# DATA_recorder.net
KiCad netlist of a schematic drawn in EasyEDA
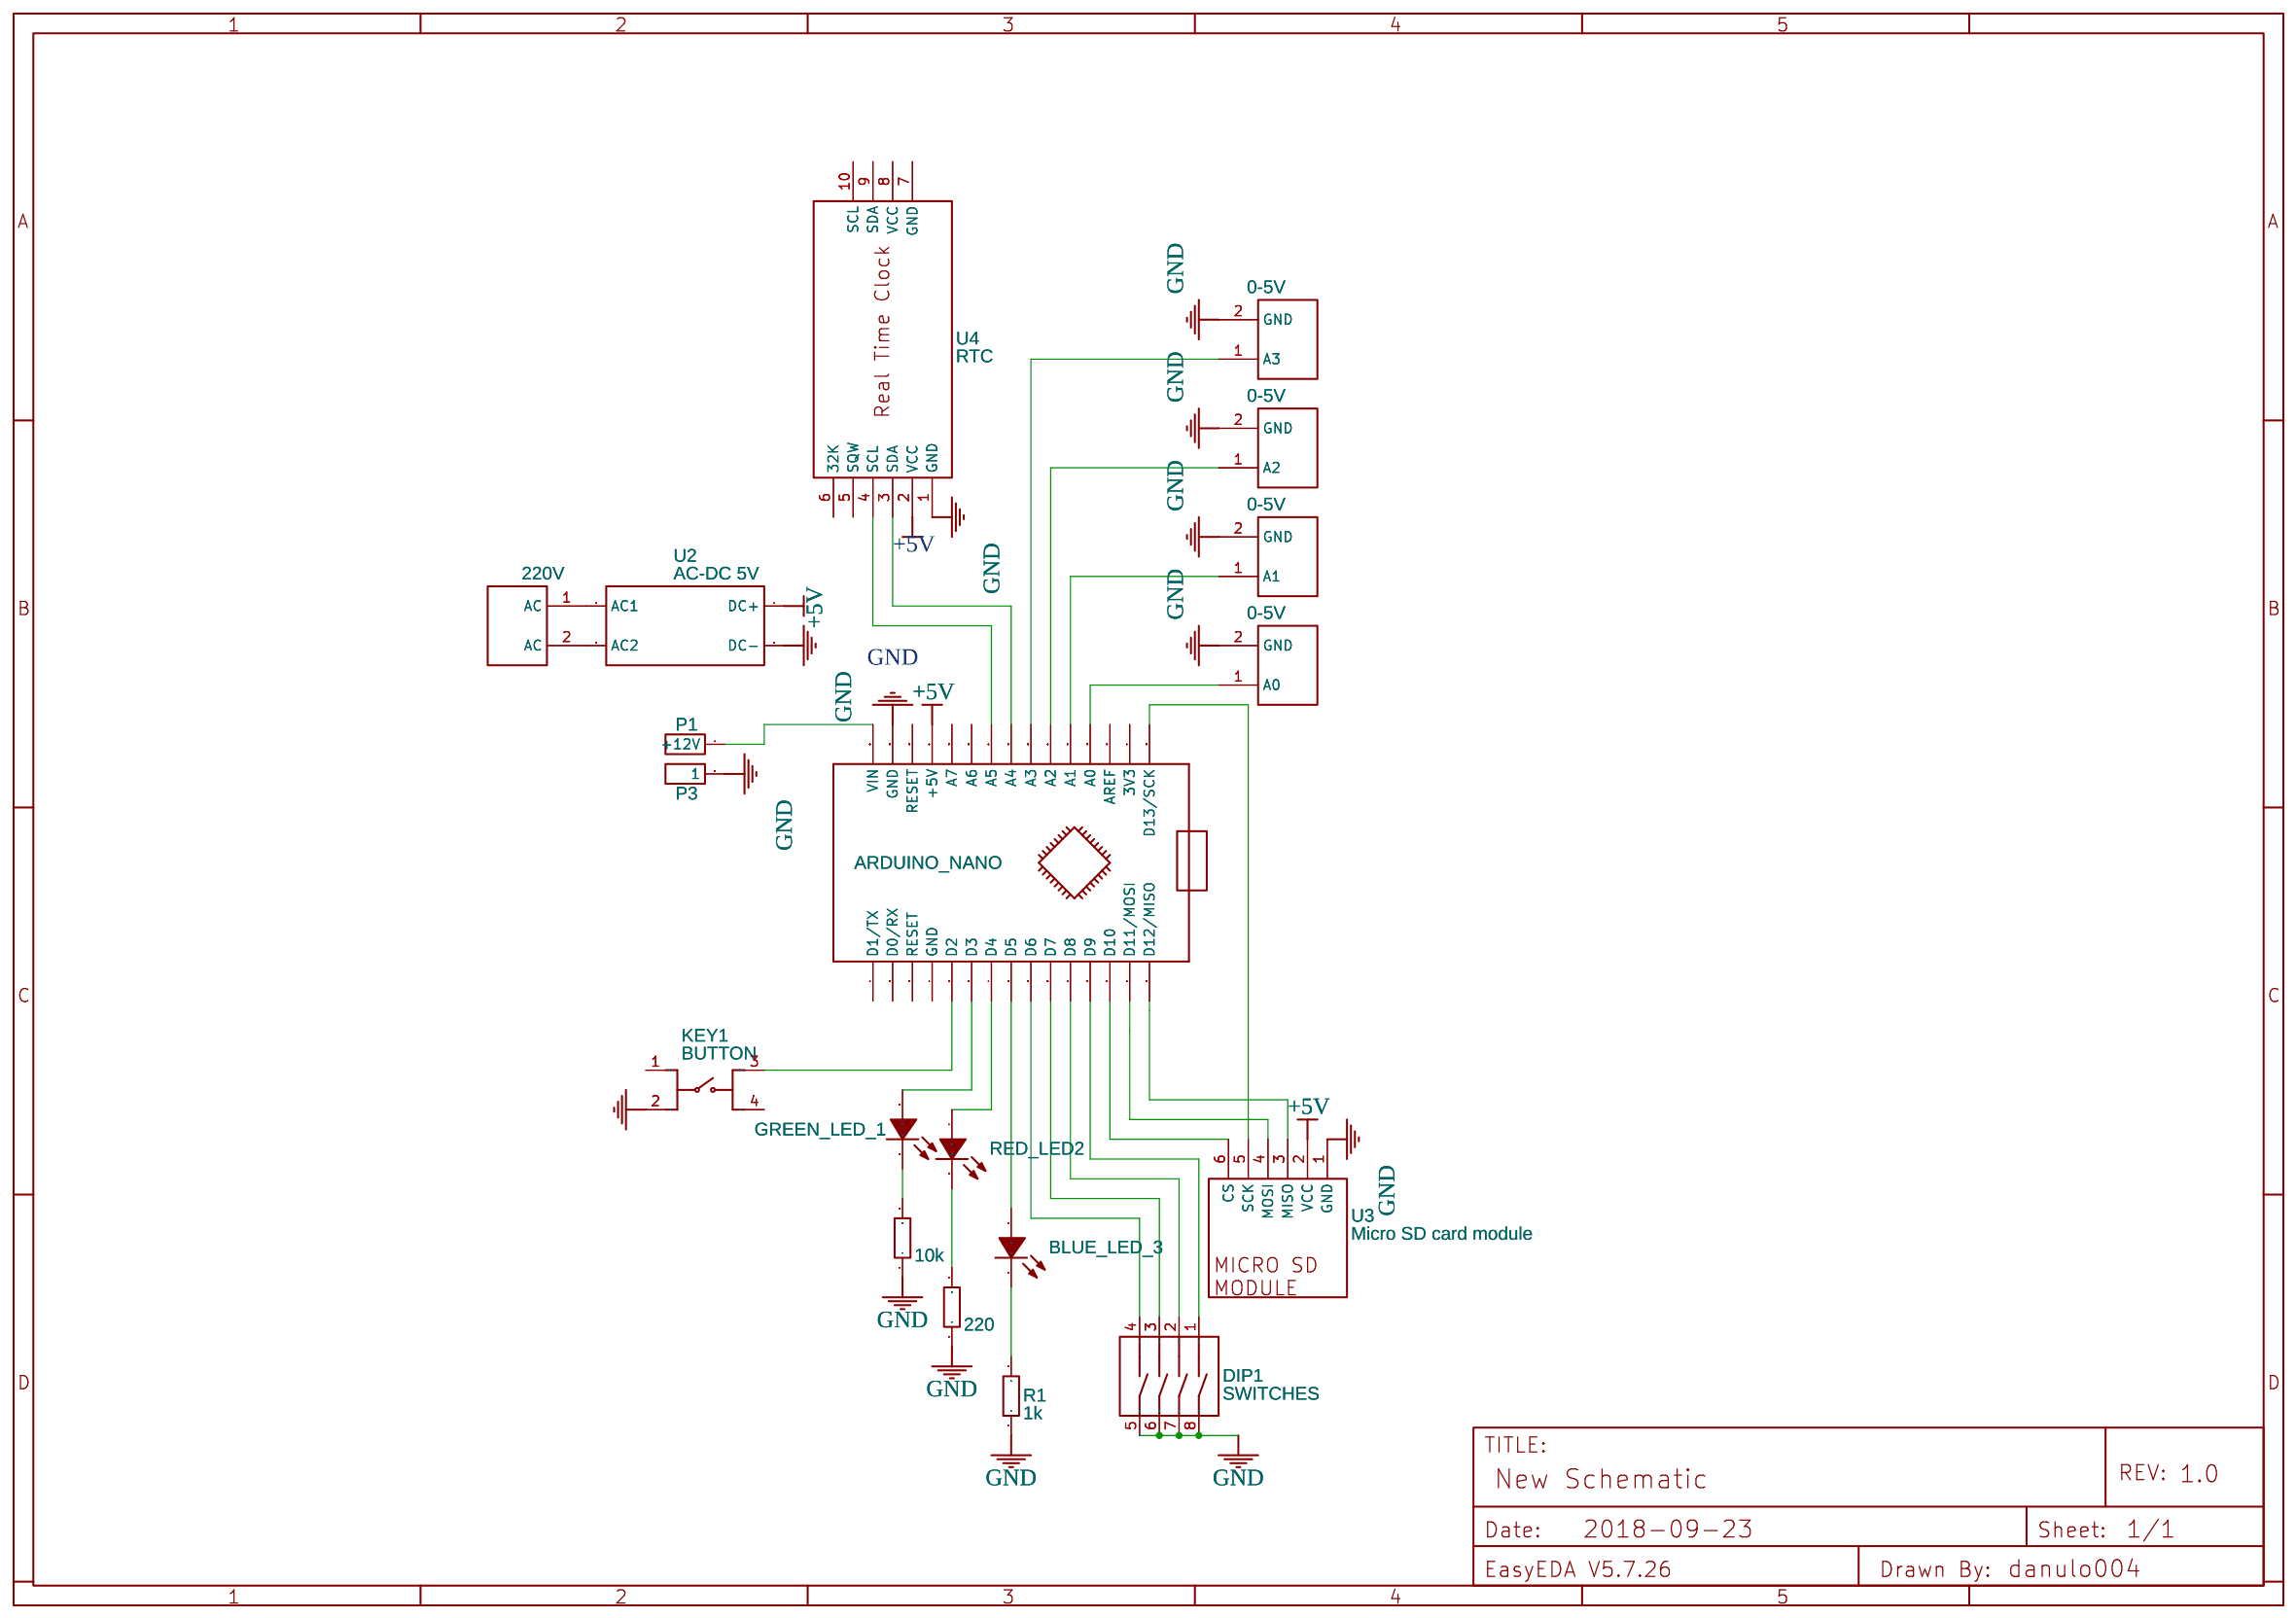
[diagram p0: schematic sheet]

(export (version "E")
  (design (tool "Eeschema 10.0.6"))
  (components
    (comp (ref "BLUE_LED_3")
      (value "LEDOrange orange 3AO4UD")
      (fields (field (name "BOM_Supplier Part") "C62095"))
      (libsource (lib "") (part "Unknown_505_625"))
    )
    (comp (ref "C")
      (value "220V")
      (fields (field (name "BOM_Manufacturer Part") "?"))
      (libsource (lib "") (part "Unknown_260_310"))
    )
    (comp (ref "CN1")
      (value "0-5V")
      (fields (field (name "BOM_Manufacturer Part") "?"))
      (libsource (lib "") (part "Unknown_640_330"))
    )
    (comp (ref "CN2")
      (value "0-5V")
      (fields (field (name "BOM_Manufacturer Part") "?"))
      (libsource (lib "") (part "Unknown_640_275"))
    )
    (comp (ref "CN3")
      (value "0-5V")
      (fields (field (name "BOM_Manufacturer Part") "?"))
      (libsource (lib "") (part "Unknown_640_220"))
    )
    (comp (ref "CN4")
      (value "0-5V")
      (fields (field (name "BOM_Manufacturer Part") "?"))
      (libsource (lib "") (part "Unknown_640_165"))
    )
    (comp (ref "DIP1")
      (value "SWITCHES")
      (fields
        (field (name "BOM_Manufacturer Part") "VDG/S-04HG-R")
        (field (name "BOM_Supplier Part") "C15781")
      )
      (libsource (lib "") (part "Unknown_585_690"))
    )
    (comp (ref "GREEN_LED_1")
      (value "LEDOrange orange 3AO4UD")
      (fields (field (name "BOM_Supplier Part") "C62095"))
      (libsource (lib "") (part "Unknown_450_565"))
    )
    (comp (ref "KEY1")
      (value "BUTTON")
      (fields
        (field (name "BOM_Manufacturer Part") "TS-1102-5016")
        (field (name "BOM_Supplier Part") "C111609")
      )
      (libsource (lib "") (part "Unknown_350_545"))
    )
    (comp (ref "P1")
      (value "Header-Male-2.54_1x1")
      (fields (field (name "BOM_Supplier Part") "C81276"))
      (libsource (lib "") (part "Unknown_345_370"))
    )
    (comp (ref "P3")
      (value "Header-Male-2.54_1x1")
      (fields (field (name "BOM_Supplier Part") "C81276"))
      (libsource (lib "") (part "Unknown_345_385"))
    )
    (comp (ref "R1")
      (value "1k")
      (fields (field (name "BOM_Manufacturer Part") "?"))
      (libsource (lib "") (part "Res_AXIAL-0.4(1/4W)_EU"))
    )
    (comp (ref "R2")
      (value "220")
      (fields (field (name "BOM_Manufacturer Part") "?"))
      (libsource (lib "") (part "Res_AXIAL-0.4(1/4W)_EU"))
    )
    (comp (ref "R3")
      (value "10k")
      (fields (field (name "BOM_Manufacturer Part") "?"))
      (libsource (lib "") (part "Res_AXIAL-0.4(1/4W)_EU"))
    )
    (comp (ref "RED_LED2")
      (value "LEDOrange orange 3AO4UD")
      (fields (field (name "BOM_Supplier Part") "C62095"))
      (libsource (lib "") (part "Unknown_475_575"))
    )
    (comp (ref "U1")
      (value "ARDUINO_NANO")
      (fields (field (name "BOM_Manufacturer Part") "?"))
      (libsource (lib "") (part "Unknown_505_430"))
    )
    (comp (ref "U2")
      (value "AC-DC 5V")
      (fields (field (name "BOM_Manufacturer Part") "?"))
      (libsource (lib "") (part "Unknown_330_310"))
    )
    (comp (ref "U3")
      (value "Micro SD card module")
      (fields (field (name "BOM_Manufacturer Part") "?"))
      (libsource (lib "") (part "Unknown_675_590"))
    )
    (comp (ref "U4")
      (value "RTC")
      (fields (field (name "BOM_Manufacturer Part") "?"))
      (libsource (lib "") (part "Unknown_425_255"))
    )
  )
  (nets
    (net (code "1") (name "+5V") (class "Default")
      (node (ref "U1") (pin "27") (pinfunction "+5V_27") (pintype "unspecified"))
      (node (ref "U2") (pin "4") (pinfunction "DC+_4") (pintype "unspecified"))
      (node (ref "U3") (pin "2") (pinfunction "VCC_2") (pintype "unspecified"))
      (node (ref "U4") (pin "2") (pinfunction "VCC_2") (pintype "unspecified"))
    )
    (net (code "2") (name "GND") (class "Default")
      (node (ref "CN1") (pin "2") (pinfunction "GND_2") (pintype "unspecified"))
      (node (ref "CN2") (pin "2") (pinfunction "GND_2") (pintype "unspecified"))
      (node (ref "CN3") (pin "2") (pinfunction "GND_2") (pintype "unspecified"))
      (node (ref "CN4") (pin "2") (pinfunction "GND_2") (pintype "unspecified"))
      (node (ref "DIP1") (pin "5") (pinfunction "5_5") (pintype "unspecified"))
      (node (ref "DIP1") (pin "6") (pinfunction "6_6") (pintype "unspecified"))
      (node (ref "DIP1") (pin "7") (pinfunction "7_7") (pintype "unspecified"))
      (node (ref "DIP1") (pin "8") (pinfunction "8_8") (pintype "unspecified"))
      (node (ref "KEY1") (pin "2") (pinfunction "2_2") (pintype "unspecified"))
      (node (ref "P3") (pin "1") (pinfunction "1_1") (pintype "input"))
      (node (ref "R1") (pin "1") (pinfunction "1_1") (pintype "unspecified"))
      (node (ref "R2") (pin "1") (pinfunction "1_1") (pintype "unspecified"))
      (node (ref "R3") (pin "1") (pinfunction "1_1") (pintype "unspecified"))
      (node (ref "U1") (pin "29") (pinfunction "GND_29") (pintype "unspecified"))
      (node (ref "U2") (pin "3") (pinfunction "DC-_3") (pintype "unspecified"))
      (node (ref "U3") (pin "1") (pinfunction "GND_1") (pintype "unspecified"))
      (node (ref "U4") (pin "1") (pinfunction "GND_1") (pintype "unspecified"))
    )
    (net (code "3") (name "Net-(BLUE_LED_3-A)") (class "Default")
      (node (ref "BLUE_LED_3") (pin "1") (pinfunction "A_1") (pintype "unspecified"))
      (node (ref "U1") (pin "8") (pinfunction "D5_8") (pintype "unspecified"))
    )
    (net (code "4") (name "Net-(BLUE_LED_3-K)") (class "Default")
      (node (ref "BLUE_LED_3") (pin "2") (pinfunction "K_2") (pintype "unspecified"))
      (node (ref "R1") (pin "2") (pinfunction "2_2") (pintype "unspecified"))
    )
    (net (code "5") (name "Net-(CN1-A0)") (class "Default")
      (node (ref "CN1") (pin "1") (pinfunction "A0_1") (pintype "unspecified"))
      (node (ref "U1") (pin "19") (pinfunction "A0_19") (pintype "unspecified"))
    )
    (net (code "6") (name "Net-(CN2-A1)") (class "Default")
      (node (ref "CN2") (pin "1") (pinfunction "A1_1") (pintype "unspecified"))
      (node (ref "U1") (pin "20") (pinfunction "A1_20") (pintype "unspecified"))
    )
    (net (code "7") (name "Net-(CN3-A2)") (class "Default")
      (node (ref "CN3") (pin "1") (pinfunction "A2_1") (pintype "unspecified"))
      (node (ref "U1") (pin "21") (pinfunction "A2_21") (pintype "unspecified"))
    )
    (net (code "8") (name "Net-(CN4-A3)") (class "Default")
      (node (ref "CN4") (pin "1") (pinfunction "A3_1") (pintype "unspecified"))
      (node (ref "U1") (pin "22") (pinfunction "A3_22") (pintype "unspecified"))
    )
    (net (code "9") (name "Net-(GREEN_LED_1-A)") (class "Default")
      (node (ref "GREEN_LED_1") (pin "1") (pinfunction "A_1") (pintype "unspecified"))
      (node (ref "U1") (pin "6") (pinfunction "D3_6") (pintype "unspecified"))
    )
    (net (code "10") (name "Net-(GREEN_LED_1-K)") (class "Default")
      (node (ref "GREEN_LED_1") (pin "2") (pinfunction "K_2") (pintype "unspecified"))
      (node (ref "R3") (pin "2") (pinfunction "2_2") (pintype "unspecified"))
    )
    (net (code "11") (name "Net-(P1-+12V)") (class "Default")
      (node (ref "P1") (pin "1") (pinfunction "+12V_1") (pintype "input"))
      (node (ref "U1") (pin "30") (pinfunction "VIN_30") (pintype "unspecified"))
    )
    (net (code "12") (name "Net-(RED_LED2-A)") (class "Default")
      (node (ref "RED_LED2") (pin "1") (pinfunction "A_1") (pintype "unspecified"))
      (node (ref "U1") (pin "7") (pinfunction "D4_7") (pintype "unspecified"))
    )
    (net (code "13") (name "Net-(RED_LED2-K)") (class "Default")
      (node (ref "R2") (pin "2") (pinfunction "2_2") (pintype "unspecified"))
      (node (ref "RED_LED2") (pin "2") (pinfunction "K_2") (pintype "unspecified"))
    )
    (net (code "14") (name "Net-(U1-A4)") (class "Default")
      (node (ref "U1") (pin "23") (pinfunction "A4_23") (pintype "unspecified"))
      (node (ref "U4") (pin "3") (pinfunction "SDA_3") (pintype "unspecified"))
    )
    (net (code "15") (name "Net-(U1-A5)") (class "Default")
      (node (ref "U1") (pin "24") (pinfunction "A5_24") (pintype "unspecified"))
      (node (ref "U4") (pin "4") (pinfunction "SCL_4") (pintype "unspecified"))
    )
    (net (code "16") (name "Net-(U1-D2)") (class "Default")
      (node (ref "KEY1") (pin "3") (pinfunction "3_3") (pintype "unspecified"))
      (node (ref "U1") (pin "5") (pinfunction "D2_5") (pintype "unspecified"))
    )
    (net (code "17") (name "Net-(U1-D6)") (class "Default")
      (node (ref "DIP1") (pin "4") (pinfunction "4_4") (pintype "unspecified"))
      (node (ref "U1") (pin "9") (pinfunction "D6_9") (pintype "unspecified"))
    )
    (net (code "18") (name "Net-(U1-D7)") (class "Default")
      (node (ref "DIP1") (pin "3") (pinfunction "3_3") (pintype "unspecified"))
      (node (ref "U1") (pin "10") (pinfunction "D7_10") (pintype "unspecified"))
    )
    (net (code "19") (name "Net-(U1-D8)") (class "Default")
      (node (ref "DIP1") (pin "2") (pinfunction "2_2") (pintype "unspecified"))
      (node (ref "U1") (pin "11") (pinfunction "D8_11") (pintype "unspecified"))
    )
    (net (code "20") (name "Net-(U1-D9)") (class "Default")
      (node (ref "DIP1") (pin "1") (pinfunction "1_1") (pintype "unspecified"))
      (node (ref "U1") (pin "12") (pinfunction "D9_12") (pintype "unspecified"))
    )
    (net (code "21") (name "Net-(U1-D10)") (class "Default")
      (node (ref "U1") (pin "13") (pinfunction "D10_13") (pintype "unspecified"))
      (node (ref "U3") (pin "6") (pinfunction "CS_6") (pintype "unspecified"))
    )
    (net (code "22") (name "Net-(U1-D11{slash}MOSI)") (class "Default")
      (node (ref "U1") (pin "14") (pinfunction "D11/MOSI_14") (pintype "unspecified"))
      (node (ref "U3") (pin "4") (pinfunction "MOSI_4") (pintype "unspecified"))
    )
    (net (code "23") (name "Net-(U1-D12{slash}MISO)") (class "Default")
      (node (ref "U1") (pin "15") (pinfunction "D12/MISO_15") (pintype "unspecified"))
      (node (ref "U3") (pin "3") (pinfunction "MISO_3") (pintype "unspecified"))
    )
    (net (code "24") (name "Net-(U1-D13{slash}SCK)") (class "Default")
      (node (ref "U1") (pin "16") (pinfunction "D13/SCK_16") (pintype "unspecified"))
      (node (ref "U3") (pin "5") (pinfunction "SCK_5") (pintype "unspecified"))
    )
    (net (code "25") (name "Net-(U2-AC1)") (class "Default")
      (node (ref "C") (pin "1") (pinfunction "AC_1") (pintype "unspecified"))
      (node (ref "U2") (pin "1") (pinfunction "AC1_1") (pintype "input"))
    )
    (net (code "26") (name "Net-(U2-AC2)") (class "Default")
      (node (ref "C") (pin "2") (pinfunction "AC_2") (pintype "unspecified"))
      (node (ref "U2") (pin "2") (pinfunction "AC2_2") (pintype "input"))
    )
    (net (code "27") (name "unconnected-(KEY1-Pad1)") (class "Default")
      (node (ref "KEY1") (pin "1") (pinfunction "1_1") (pintype "unspecified"))
    )
    (net (code "28") (name "unconnected-(KEY1-Pad4)") (class "Default")
      (node (ref "KEY1") (pin "4") (pinfunction "4_4") (pintype "unspecified"))
    )
    (net (code "29") (name "unconnected-(U1-3V3-Pad17)") (class "Default")
      (node (ref "U1") (pin "17") (pinfunction "3V3_17") (pintype "unspecified"))
    )
    (net (code "30") (name "unconnected-(U1-A6-Pad25)") (class "Default")
      (node (ref "U1") (pin "25") (pinfunction "A6_25") (pintype "unspecified"))
    )
    (net (code "31") (name "unconnected-(U1-A7-Pad26)") (class "Default")
      (node (ref "U1") (pin "26") (pinfunction "A7_26") (pintype "unspecified"))
    )
    (net (code "32") (name "unconnected-(U1-AREF-Pad18)") (class "Default")
      (node (ref "U1") (pin "18") (pinfunction "AREF_18") (pintype "unspecified"))
    )
    (net (code "33") (name "unconnected-(U1-D0{slash}RX-Pad2)") (class "Default")
      (node (ref "U1") (pin "2") (pinfunction "D0/RX_2") (pintype "unspecified"))
    )
    (net (code "34") (name "unconnected-(U1-D1{slash}TX-Pad1)") (class "Default")
      (node (ref "U1") (pin "1") (pinfunction "D1/TX_1") (pintype "unspecified"))
    )
    (net (code "35") (name "unconnected-(U1-GND-Pad4)") (class "Default")
      (node (ref "U1") (pin "4") (pinfunction "GND_4") (pintype "unspecified"))
    )
    (net (code "36") (name "unconnected-(U1-RESET-Pad3)") (class "Default")
      (node (ref "U1") (pin "3") (pinfunction "RESET_3") (pintype "unspecified"))
    )
    (net (code "37") (name "unconnected-(U1-RESET-Pad28)") (class "Default")
      (node (ref "U1") (pin "28") (pinfunction "RESET_28") (pintype "unspecified"))
    )
    (net (code "38") (name "unconnected-(U4-32K-Pad6)") (class "Default")
      (node (ref "U4") (pin "6") (pinfunction "32K_6") (pintype "unspecified"))
    )
    (net (code "39") (name "unconnected-(U4-GND-Pad7)") (class "Default")
      (node (ref "U4") (pin "7") (pinfunction "GND_7") (pintype "unspecified"))
    )
    (net (code "40") (name "unconnected-(U4-SCL-Pad10)") (class "Default")
      (node (ref "U4") (pin "10") (pinfunction "SCL_10") (pintype "unspecified"))
    )
    (net (code "41") (name "unconnected-(U4-SDA-Pad9)") (class "Default")
      (node (ref "U4") (pin "9") (pinfunction "SDA_9") (pintype "unspecified"))
    )
    (net (code "42") (name "unconnected-(U4-SQW-Pad5)") (class "Default")
      (node (ref "U4") (pin "5") (pinfunction "SQW_5") (pintype "unspecified"))
    )
    (net (code "43") (name "unconnected-(U4-VCC-Pad8)") (class "Default")
      (node (ref "U4") (pin "8") (pinfunction "VCC_8") (pintype "unspecified"))
    )
  )
)
